# Motor_Driver2.net
KiCad netlist of a schematic drawn in Altium Designer
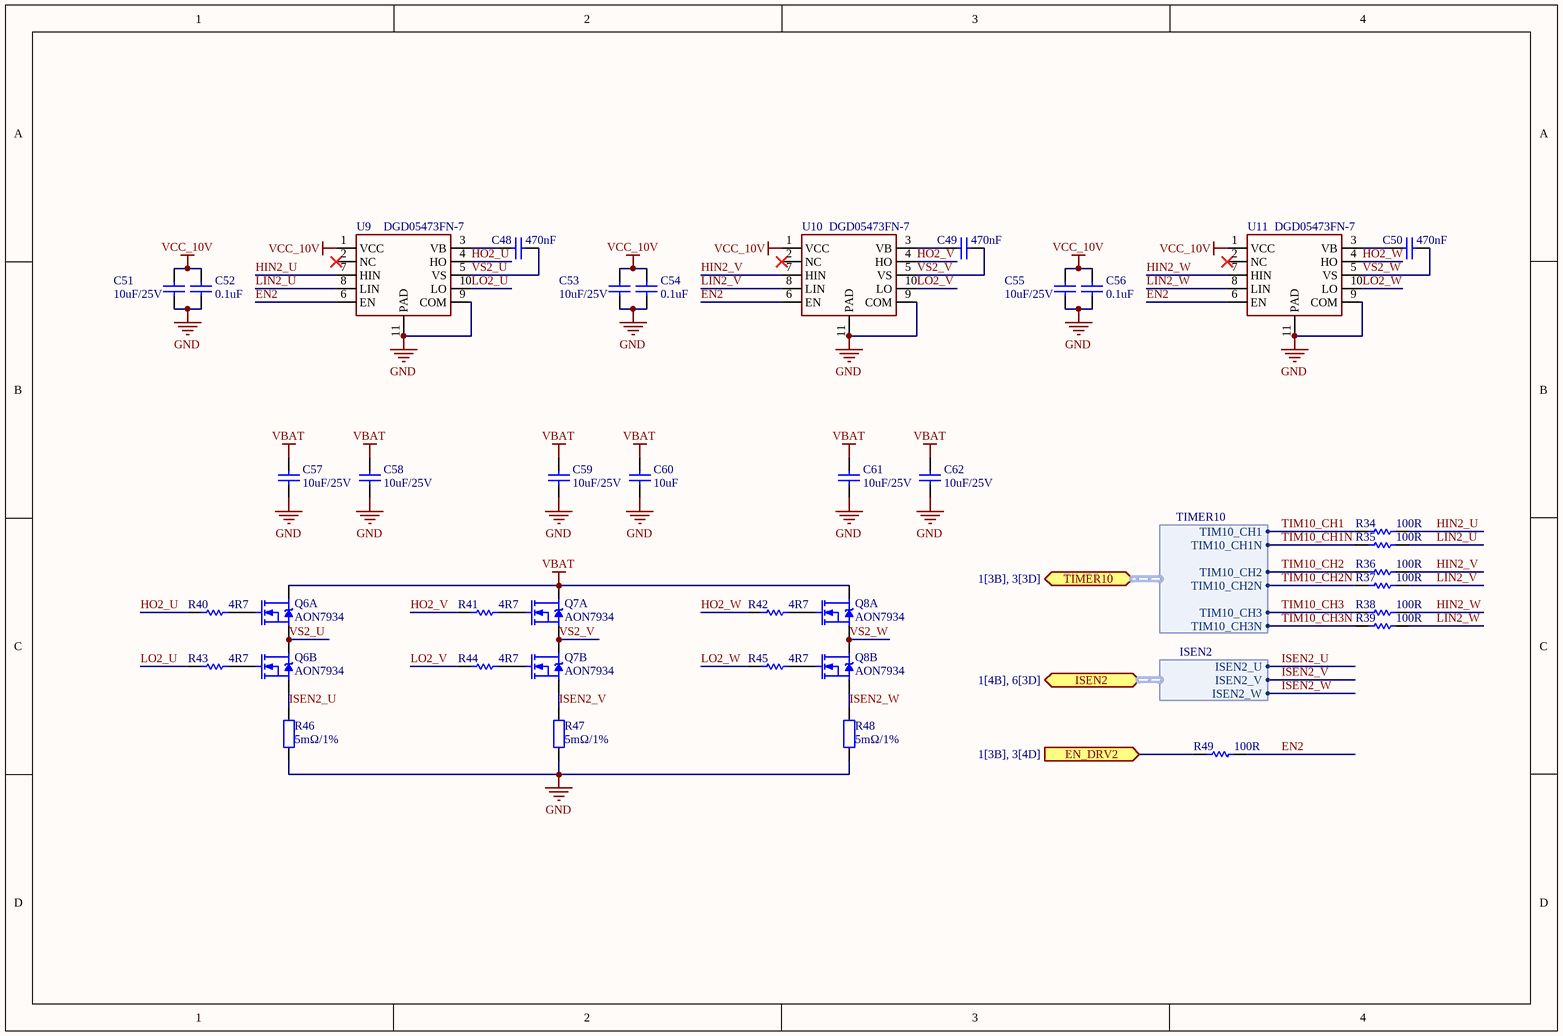
[diagram p0: Motor_Driver2.SchDoc]

(export (version "E")
  (design (tool "Eeschema 10.0.6"))
  (components
    (comp (ref "C48")
      (value "470nF")
      (footprint "C0603_NS")
      (description "Capacitor")
      (fields (field (name "PUBLISHER") "Altium Limited"))
      (libsource (lib "Miscellaneous Devices") (part "Cap"))
    )
    (comp (ref "C49")
      (value "470nF")
      (footprint "C0603_NS")
      (description "Capacitor")
      (fields (field (name "PUBLISHER") "Altium Limited"))
      (libsource (lib "Miscellaneous Devices") (part "Cap"))
    )
    (comp (ref "C50")
      (value "470nF")
      (footprint "C0603_NS")
      (description "Capacitor")
      (fields (field (name "PUBLISHER") "Altium Limited"))
      (libsource (lib "Miscellaneous Devices") (part "Cap"))
    )
    (comp (ref "C51")
      (value "10uF/25V")
      (footprint "C0603_NS")
      (description "Capacitor")
      (fields (field (name "PUBLISHER") "Altium Limited"))
      (libsource (lib "Miscellaneous Devices") (part "Cap"))
    )
    (comp (ref "C52")
      (value "0.1uF")
      (footprint "C0603_NS")
      (description "Capacitor")
      (fields (field (name "PUBLISHER") "Altium Limited"))
      (libsource (lib "Miscellaneous Devices") (part "Cap"))
    )
    (comp (ref "C53")
      (value "10uF/25V")
      (footprint "C0603_NS")
      (description "Capacitor")
      (fields (field (name "PUBLISHER") "Altium Limited"))
      (libsource (lib "Miscellaneous Devices") (part "Cap"))
    )
    (comp (ref "C54")
      (value "0.1uF")
      (footprint "C0603_NS")
      (description "Capacitor")
      (fields (field (name "PUBLISHER") "Altium Limited"))
      (libsource (lib "Miscellaneous Devices") (part "Cap"))
    )
    (comp (ref "C55")
      (value "10uF/25V")
      (footprint "C0603_NS")
      (description "Capacitor")
      (fields (field (name "PUBLISHER") "Altium Limited"))
      (libsource (lib "Miscellaneous Devices") (part "Cap"))
    )
    (comp (ref "C56")
      (value "0.1uF")
      (footprint "C0603_NS")
      (description "Capacitor")
      (fields (field (name "PUBLISHER") "Altium Limited"))
      (libsource (lib "Miscellaneous Devices") (part "Cap"))
    )
    (comp (ref "C57")
      (value "10uF/25V")
      (footprint "C0603_NS")
      (description "Capacitor")
      (libsource (lib "Miscellaneous Devices") (part "Cap"))
    )
    (comp (ref "C58")
      (value "10uF/25V")
      (footprint "C0603_NS")
      (description "Capacitor")
      (libsource (lib "Miscellaneous Devices") (part "Cap"))
    )
    (comp (ref "C59")
      (value "10uF/25V")
      (footprint "C0603_NS")
      (description "Capacitor")
      (libsource (lib "Miscellaneous Devices") (part "Cap"))
    )
    (comp (ref "C60")
      (value "10uF")
      (footprint "C0603_NS")
      (description "Capacitor")
      (libsource (lib "Miscellaneous Devices") (part "Cap"))
    )
    (comp (ref "C61")
      (value "10uF/25V")
      (footprint "C0603_NS")
      (description "Capacitor")
      (libsource (lib "Miscellaneous Devices") (part "Cap"))
    )
    (comp (ref "C62")
      (value "10uF/25V")
      (footprint "C0603_NS")
      (description "Capacitor")
      (libsource (lib "Miscellaneous Devices") (part "Cap"))
    )
    (comp (ref "Q6")
      (value "AON7934")
      (footprint "POWERPAIR_3X3")
      (libsource (lib "my_library") (part "AON7934"))
    )
    (comp (ref "Q7")
      (value "AON7934")
      (footprint "POWERPAIR_3X3")
      (libsource (lib "my_library") (part "AON7934"))
    )
    (comp (ref "Q8")
      (value "AON7934")
      (footprint "POWERPAIR_3X3")
      (libsource (lib "my_library") (part "AON7934"))
    )
    (comp (ref "R34")
      (value "100R")
      (footprint "R0603_NS")
      (description "Resistor")
      (libsource (lib "Miscellaneous Devices") (part "Res1"))
    )
    (comp (ref "R35")
      (value "100R")
      (footprint "R0603_NS")
      (description "Resistor")
      (libsource (lib "Miscellaneous Devices") (part "Res1"))
    )
    (comp (ref "R36")
      (value "100R")
      (footprint "R0603_NS")
      (description "Resistor")
      (libsource (lib "Miscellaneous Devices") (part "Res1"))
    )
    (comp (ref "R37")
      (value "100R")
      (footprint "R0603_NS")
      (description "Resistor")
      (libsource (lib "Miscellaneous Devices") (part "Res1"))
    )
    (comp (ref "R38")
      (value "100R")
      (footprint "R0603_NS")
      (description "Resistor")
      (libsource (lib "Miscellaneous Devices") (part "Res1"))
    )
    (comp (ref "R39")
      (value "100R")
      (footprint "R0603_NS")
      (description "Resistor")
      (libsource (lib "Miscellaneous Devices") (part "Res1"))
    )
    (comp (ref "R40")
      (value "4R7")
      (footprint "R0603_NS")
      (description "Resistor")
      (libsource (lib "Miscellaneous Devices") (part "Res1"))
    )
    (comp (ref "R41")
      (value "4R7")
      (footprint "R0603_NS")
      (description "Resistor")
      (libsource (lib "Miscellaneous Devices") (part "Res1"))
    )
    (comp (ref "R42")
      (value "4R7")
      (footprint "R0603_NS")
      (description "Resistor")
      (libsource (lib "Miscellaneous Devices") (part "Res1"))
    )
    (comp (ref "R43")
      (value "4R7")
      (footprint "R0603_NS")
      (description "Resistor")
      (libsource (lib "Miscellaneous Devices") (part "Res1"))
    )
    (comp (ref "R44")
      (value "4R7")
      (footprint "R0603_NS")
      (description "Resistor")
      (libsource (lib "Miscellaneous Devices") (part "Res1"))
    )
    (comp (ref "R45")
      (value "4R7")
      (footprint "R0603_NS")
      (description "Resistor")
      (libsource (lib "Miscellaneous Devices") (part "Res1"))
    )
    (comp (ref "R46")
      (value "5mΩ/1%")
      (footprint "R1206_NS")
      (description "Resistor")
      (fields (field (name "PUBLISHER") "Altium Limited"))
      (libsource (lib "Miscellaneous Devices") (part "Res2"))
    )
    (comp (ref "R47")
      (value "5mΩ/1%")
      (footprint "R1206_NS")
      (description "Resistor")
      (fields (field (name "PUBLISHER") "Altium Limited"))
      (libsource (lib "Miscellaneous Devices") (part "Res2"))
    )
    (comp (ref "R48")
      (value "5mΩ/1%")
      (footprint "R1206_NS")
      (description "Resistor")
      (fields (field (name "PUBLISHER") "Altium Limited"))
      (libsource (lib "Miscellaneous Devices") (part "Res2"))
    )
    (comp (ref "R49")
      (value "100R")
      (footprint "R0603_NS")
      (description "Resistor")
      (libsource (lib "Miscellaneous Devices") (part "Res1"))
    )
    (comp (ref "U9")
      (value "DGD05473FN-7")
      (footprint "W-DFN3030-10_DGD05473")
      (libsource (lib "my_library") (part "DGD05473"))
    )
    (comp (ref "U10")
      (value "DGD05473FN-7")
      (footprint "W-DFN3030-10_DGD05473")
      (libsource (lib "my_library") (part "DGD05473"))
    )
    (comp (ref "U11")
      (value "DGD05473FN-7")
      (footprint "W-DFN3030-10_DGD05473")
      (libsource (lib "my_library") (part "DGD05473"))
    )
  )
  (nets
    (net (code "3") (name "/EN2") (class "Default")
      (node (ref "R49") (pin "2") (pinfunction "2_2") (pintype "passive"))
      (node (ref "U10") (pin "6") (pinfunction "EN_6") (pintype "passive"))
      (node (ref "U11") (pin "6") (pinfunction "EN_6") (pintype "passive"))
      (node (ref "U9") (pin "6") (pinfunction "EN_6") (pintype "passive"))
    )
    (net (code "4") (name "/EN_DRV2") (class "Default")
      (node (ref "R49") (pin "1") (pinfunction "1_1") (pintype "passive"))
    )
    (net (code "5") (name "/HIN2_U") (class "Default")
      (node (ref "R34") (pin "2") (pinfunction "2_2") (pintype "passive"))
      (node (ref "U9") (pin "7") (pinfunction "HIN_7") (pintype "passive"))
    )
    (net (code "6") (name "/HIN2_V") (class "Default")
      (node (ref "R36") (pin "2") (pinfunction "2_2") (pintype "passive"))
      (node (ref "U10") (pin "7") (pinfunction "HIN_7") (pintype "passive"))
    )
    (net (code "7") (name "/HIN2_W") (class "Default")
      (node (ref "R38") (pin "2") (pinfunction "2_2") (pintype "passive"))
      (node (ref "U11") (pin "7") (pinfunction "HIN_7") (pintype "passive"))
    )
    (net (code "8") (name "/HO2_U") (class "Default")
      (node (ref "R40") (pin "1") (pinfunction "1_1") (pintype "passive"))
      (node (ref "U9") (pin "4") (pinfunction "HO_4") (pintype "passive"))
    )
    (net (code "9") (name "/HO2_V") (class "Default")
      (node (ref "R41") (pin "1") (pinfunction "1_1") (pintype "passive"))
      (node (ref "U10") (pin "4") (pinfunction "HO_4") (pintype "passive"))
    )
    (net (code "10") (name "/HO2_W") (class "Default")
      (node (ref "R42") (pin "1") (pinfunction "1_1") (pintype "passive"))
      (node (ref "U11") (pin "4") (pinfunction "HO_4") (pintype "passive"))
    )
    (net (code "11") (name "/ISEN2_U") (class "Default")
      (node (ref "Q6") (pin "S2") (pinfunction "S2_S2") (pintype "passive"))
      (node (ref "R46") (pin "2") (pinfunction "2_2") (pintype "passive"))
    )
    (net (code "12") (name "/ISEN2_V") (class "Default")
      (node (ref "Q7") (pin "S2") (pinfunction "S2_S2") (pintype "passive"))
      (node (ref "R47") (pin "2") (pinfunction "2_2") (pintype "passive"))
    )
    (net (code "13") (name "/ISEN2_W") (class "Default")
      (node (ref "Q8") (pin "S2") (pinfunction "S2_S2") (pintype "passive"))
      (node (ref "R48") (pin "2") (pinfunction "2_2") (pintype "passive"))
    )
    (net (code "14") (name "/LIN2_U") (class "Default")
      (node (ref "R35") (pin "2") (pinfunction "2_2") (pintype "passive"))
      (node (ref "U9") (pin "8") (pinfunction "LIN_8") (pintype "passive"))
    )
    (net (code "15") (name "/LIN2_V") (class "Default")
      (node (ref "R37") (pin "2") (pinfunction "2_2") (pintype "passive"))
      (node (ref "U10") (pin "8") (pinfunction "LIN_8") (pintype "passive"))
    )
    (net (code "16") (name "/LIN2_W") (class "Default")
      (node (ref "R39") (pin "2") (pinfunction "2_2") (pintype "passive"))
      (node (ref "U11") (pin "8") (pinfunction "LIN_8") (pintype "passive"))
    )
    (net (code "17") (name "/LO2_U") (class "Default")
      (node (ref "R43") (pin "1") (pinfunction "1_1") (pintype "passive"))
      (node (ref "U9") (pin "10") (pinfunction "LO_10") (pintype "passive"))
    )
    (net (code "18") (name "/LO2_V") (class "Default")
      (node (ref "R44") (pin "1") (pinfunction "1_1") (pintype "passive"))
      (node (ref "U10") (pin "10") (pinfunction "LO_10") (pintype "passive"))
    )
    (net (code "19") (name "/LO2_W") (class "Default")
      (node (ref "R45") (pin "1") (pinfunction "1_1") (pintype "passive"))
      (node (ref "U11") (pin "10") (pinfunction "LO_10") (pintype "passive"))
    )
    (net (code "20") (name "/TIM10_CH1") (class "Default")
      (node (ref "R34") (pin "1") (pinfunction "1_1") (pintype "passive"))
    )
    (net (code "21") (name "/TIM10_CH1N") (class "Default")
      (node (ref "R35") (pin "1") (pinfunction "1_1") (pintype "passive"))
    )
    (net (code "22") (name "/TIM10_CH2") (class "Default")
      (node (ref "R36") (pin "1") (pinfunction "1_1") (pintype "passive"))
    )
    (net (code "23") (name "/TIM10_CH2N") (class "Default")
      (node (ref "R37") (pin "1") (pinfunction "1_1") (pintype "passive"))
    )
    (net (code "24") (name "/TIM10_CH3") (class "Default")
      (node (ref "R38") (pin "1") (pinfunction "1_1") (pintype "passive"))
    )
    (net (code "25") (name "/TIM10_CH3N") (class "Default")
      (node (ref "R39") (pin "1") (pinfunction "1_1") (pintype "passive"))
    )
    (net (code "26") (name "/VS2_U") (class "Default")
      (node (ref "C48") (pin "2") (pinfunction "2_2") (pintype "passive"))
      (node (ref "Q6") (pin "S1/D2") (pinfunction "S1/D2_S1/D2") (pintype "passive"))
      (node (ref "U9") (pin "5") (pinfunction "VS_5") (pintype "passive"))
    )
    (net (code "27") (name "/VS2_V") (class "Default")
      (node (ref "C49") (pin "2") (pinfunction "2_2") (pintype "passive"))
      (node (ref "Q7") (pin "S1/D2") (pinfunction "S1/D2_S1/D2") (pintype "passive"))
      (node (ref "U10") (pin "5") (pinfunction "VS_5") (pintype "passive"))
    )
    (net (code "28") (name "/VS2_W") (class "Default")
      (node (ref "C50") (pin "2") (pinfunction "2_2") (pintype "passive"))
      (node (ref "Q8") (pin "S1/D2") (pinfunction "S1/D2_S1/D2") (pintype "passive"))
      (node (ref "U11") (pin "5") (pinfunction "VS_5") (pintype "passive"))
    )
    (net (code "31") (name "GND") (class "Default")
      (node (ref "C51") (pin "2") (pinfunction "2_2") (pintype "passive"))
      (node (ref "C52") (pin "2") (pinfunction "2_2") (pintype "passive"))
      (node (ref "C53") (pin "2") (pinfunction "2_2") (pintype "passive"))
      (node (ref "C54") (pin "2") (pinfunction "2_2") (pintype "passive"))
      (node (ref "C55") (pin "2") (pinfunction "2_2") (pintype "passive"))
      (node (ref "C56") (pin "2") (pinfunction "2_2") (pintype "passive"))
      (node (ref "C57") (pin "1") (pinfunction "1_1") (pintype "passive"))
      (node (ref "C58") (pin "1") (pinfunction "1_1") (pintype "passive"))
      (node (ref "C59") (pin "1") (pinfunction "1_1") (pintype "passive"))
      (node (ref "C60") (pin "1") (pinfunction "1_1") (pintype "passive"))
      (node (ref "C61") (pin "1") (pinfunction "1_1") (pintype "passive"))
      (node (ref "C62") (pin "1") (pinfunction "1_1") (pintype "passive"))
      (node (ref "R46") (pin "1") (pinfunction "1_1") (pintype "passive"))
      (node (ref "R47") (pin "1") (pinfunction "1_1") (pintype "passive"))
      (node (ref "R48") (pin "1") (pinfunction "1_1") (pintype "passive"))
      (node (ref "U10") (pin "11") (pinfunction "PAD_11") (pintype "passive"))
      (node (ref "U10") (pin "9") (pinfunction "COM_9") (pintype "passive"))
      (node (ref "U11") (pin "11") (pinfunction "PAD_11") (pintype "passive"))
      (node (ref "U11") (pin "9") (pinfunction "COM_9") (pintype "passive"))
      (node (ref "U9") (pin "11") (pinfunction "PAD_11") (pintype "passive"))
      (node (ref "U9") (pin "9") (pinfunction "COM_9") (pintype "passive"))
    )
    (net (code "32") (name "Net-(Q6-PadG1)") (class "Default")
      (node (ref "Q6") (pin "G1") (pinfunction "G1_G1") (pintype "passive"))
      (node (ref "R40") (pin "2") (pinfunction "2_2") (pintype "passive"))
    )
    (net (code "33") (name "Net-(Q6-PadG2)") (class "Default")
      (node (ref "Q6") (pin "G2") (pinfunction "G2_G2") (pintype "passive"))
      (node (ref "R43") (pin "2") (pinfunction "2_2") (pintype "passive"))
    )
    (net (code "34") (name "Net-(Q7-PadG1)") (class "Default")
      (node (ref "Q7") (pin "G1") (pinfunction "G1_G1") (pintype "passive"))
      (node (ref "R41") (pin "2") (pinfunction "2_2") (pintype "passive"))
    )
    (net (code "35") (name "Net-(Q7-PadG2)") (class "Default")
      (node (ref "Q7") (pin "G2") (pinfunction "G2_G2") (pintype "passive"))
      (node (ref "R44") (pin "2") (pinfunction "2_2") (pintype "passive"))
    )
    (net (code "36") (name "Net-(Q8-PadG1)") (class "Default")
      (node (ref "Q8") (pin "G1") (pinfunction "G1_G1") (pintype "passive"))
      (node (ref "R42") (pin "2") (pinfunction "2_2") (pintype "passive"))
    )
    (net (code "37") (name "Net-(Q8-PadG2)") (class "Default")
      (node (ref "Q8") (pin "G2") (pinfunction "G2_G2") (pintype "passive"))
      (node (ref "R45") (pin "2") (pinfunction "2_2") (pintype "passive"))
    )
    (net (code "38") (name "Net-(U9-VB)") (class "Default")
      (node (ref "C48") (pin "1") (pinfunction "1_1") (pintype "passive"))
      (node (ref "U9") (pin "3") (pinfunction "VB_3") (pintype "passive"))
    )
    (net (code "39") (name "Net-(U10-VB)") (class "Default")
      (node (ref "C49") (pin "1") (pinfunction "1_1") (pintype "passive"))
      (node (ref "U10") (pin "3") (pinfunction "VB_3") (pintype "passive"))
    )
    (net (code "40") (name "Net-(U11-VB)") (class "Default")
      (node (ref "C50") (pin "1") (pinfunction "1_1") (pintype "passive"))
      (node (ref "U11") (pin "3") (pinfunction "VB_3") (pintype "passive"))
    )
    (net (code "41") (name "VBAT") (class "Default")
      (node (ref "C57") (pin "2") (pinfunction "2_2") (pintype "passive"))
      (node (ref "C58") (pin "2") (pinfunction "2_2") (pintype "passive"))
      (node (ref "C59") (pin "2") (pinfunction "2_2") (pintype "passive"))
      (node (ref "C60") (pin "2") (pinfunction "2_2") (pintype "passive"))
      (node (ref "C61") (pin "2") (pinfunction "2_2") (pintype "passive"))
      (node (ref "C62") (pin "2") (pinfunction "2_2") (pintype "passive"))
      (node (ref "Q6") (pin "D1") (pinfunction "D1_D1") (pintype "passive"))
      (node (ref "Q7") (pin "D1") (pinfunction "D1_D1") (pintype "passive"))
      (node (ref "Q8") (pin "D1") (pinfunction "D1_D1") (pintype "passive"))
    )
    (net (code "42") (name "VCC_10V") (class "Default")
      (node (ref "C51") (pin "1") (pinfunction "1_1") (pintype "passive"))
      (node (ref "C52") (pin "1") (pinfunction "1_1") (pintype "passive"))
      (node (ref "C53") (pin "1") (pinfunction "1_1") (pintype "passive"))
      (node (ref "C54") (pin "1") (pinfunction "1_1") (pintype "passive"))
      (node (ref "C55") (pin "1") (pinfunction "1_1") (pintype "passive"))
      (node (ref "C56") (pin "1") (pinfunction "1_1") (pintype "passive"))
      (node (ref "U10") (pin "1") (pinfunction "VCC_1") (pintype "passive"))
      (node (ref "U11") (pin "1") (pinfunction "VCC_1") (pintype "passive"))
      (node (ref "U9") (pin "1") (pinfunction "VCC_1") (pintype "passive"))
    )
    (net (code "43") (name "unconnected-(U9-NC-Pad2)") (class "Default")
      (node (ref "U9") (pin "2") (pinfunction "NC_2") (pintype "passive+no_connect"))
    )
    (net (code "44") (name "unconnected-(U10-NC-Pad2)") (class "Default")
      (node (ref "U10") (pin "2") (pinfunction "NC_2") (pintype "passive+no_connect"))
    )
    (net (code "45") (name "unconnected-(U11-NC-Pad2)") (class "Default")
      (node (ref "U11") (pin "2") (pinfunction "NC_2") (pintype "passive+no_connect"))
    )
  )
)
